# FAN7688.net
KiCad netlist of a schematic drawn in Altium Designer
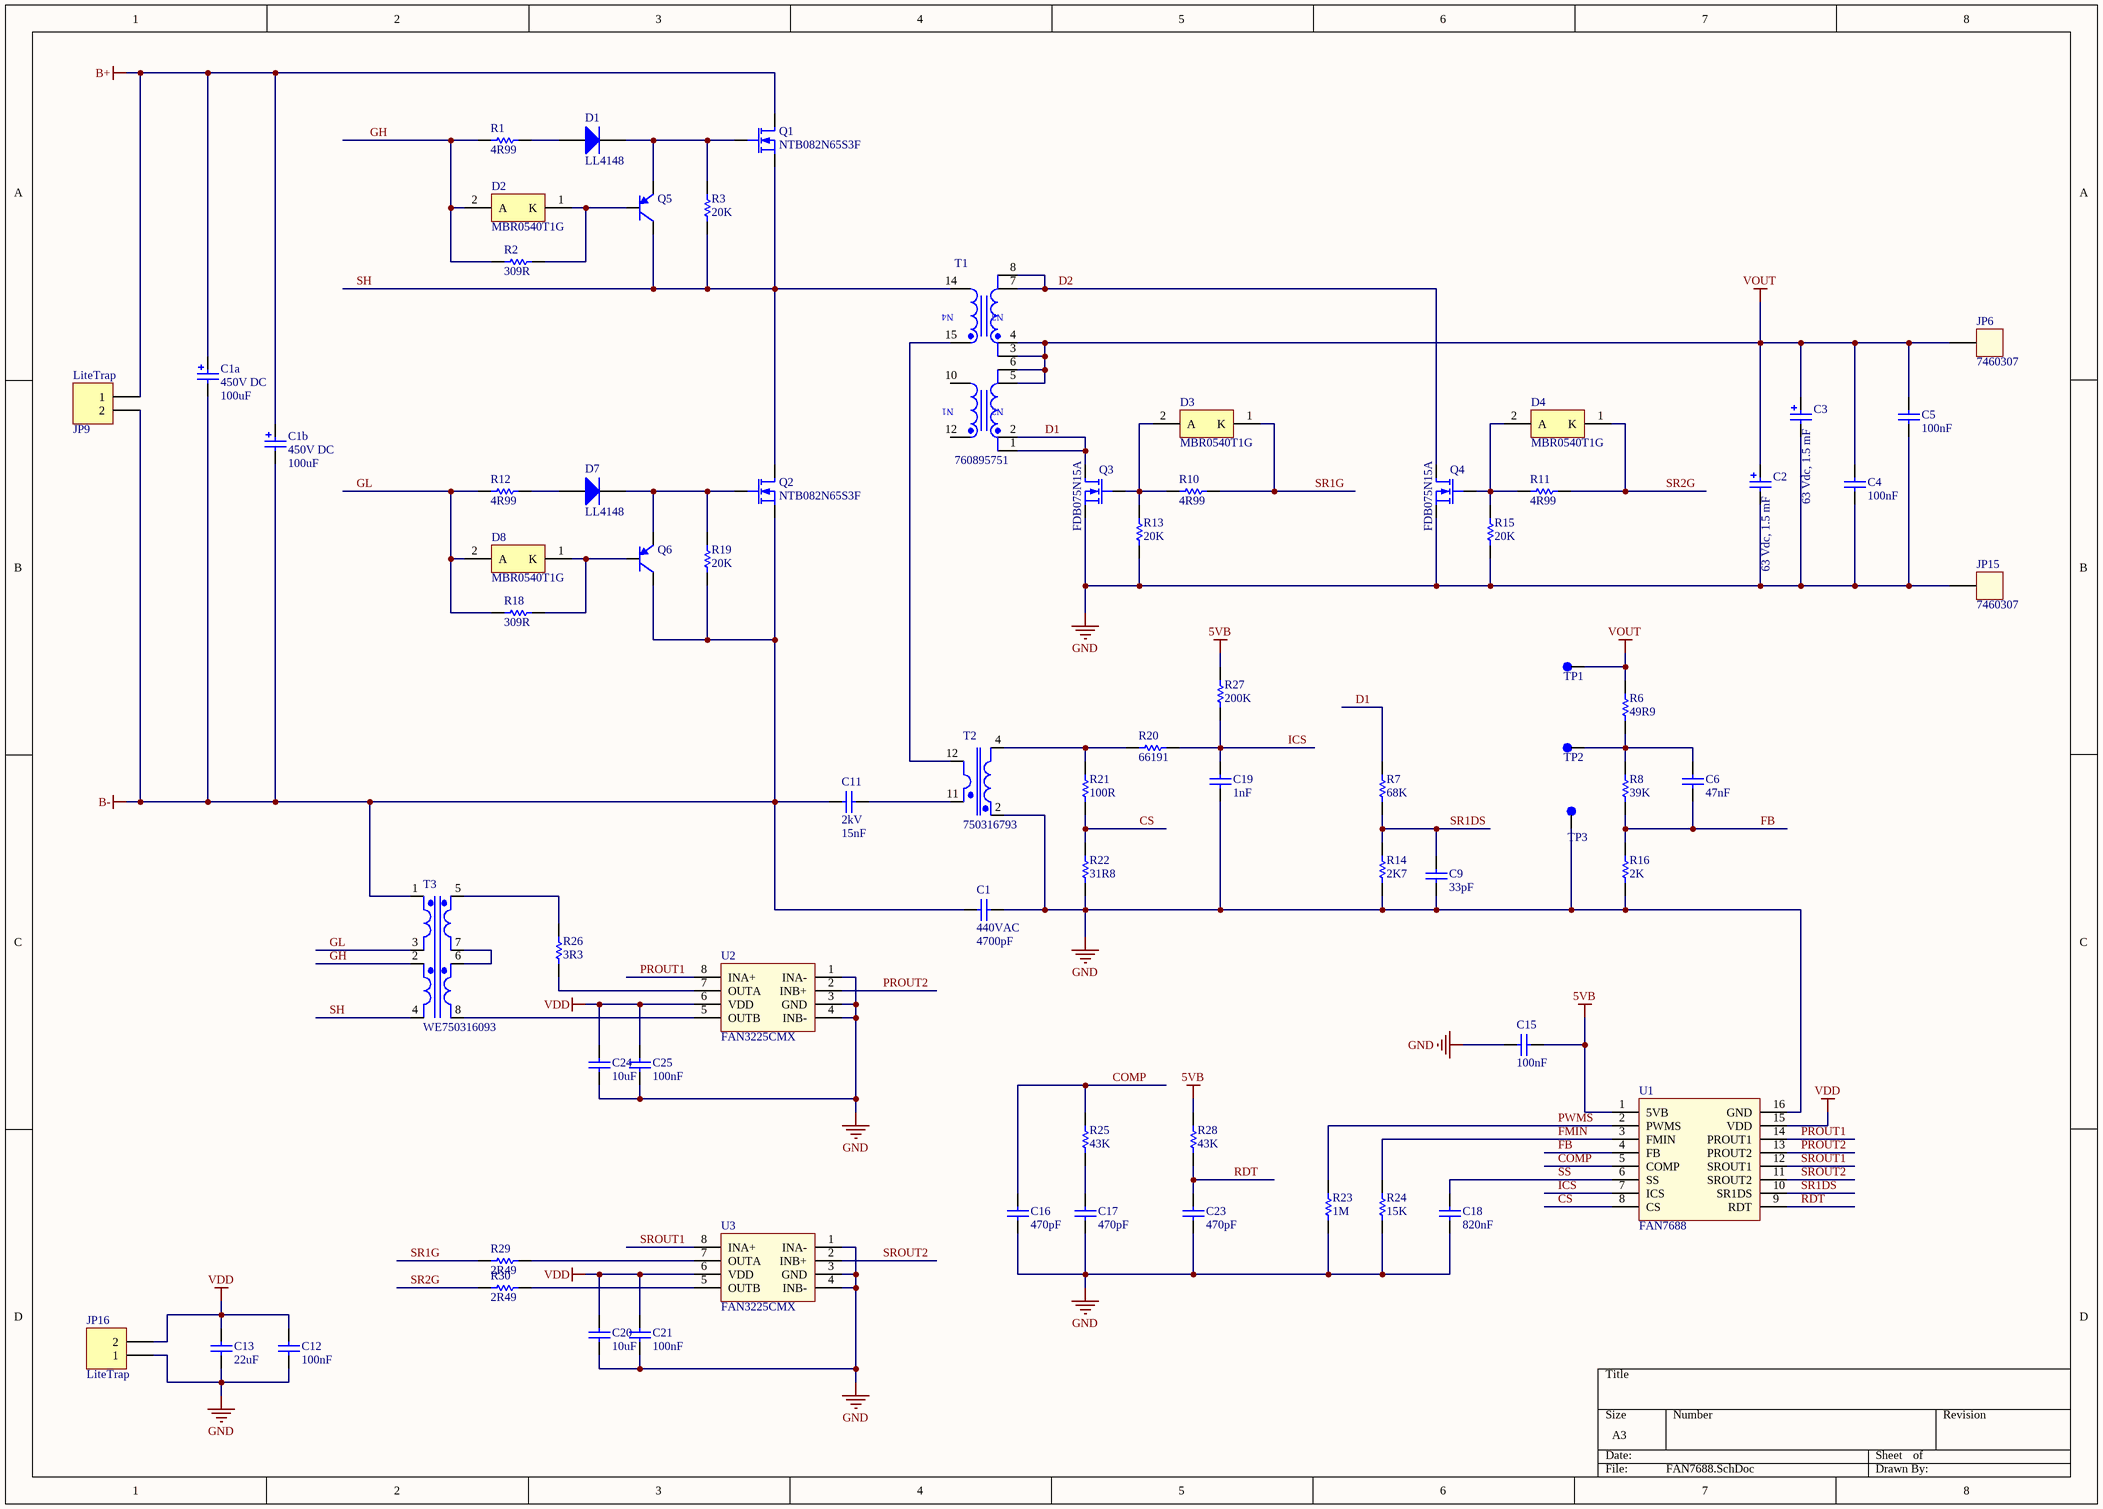
[diagram p0: FAN7688.SchDoc]

(export (version "E")
  (design (tool "Eeschema 10.0.6"))
  (components
    (comp (ref "C1")
      (value "4700pF")
      (footprint "CAP_VY2472M49Y5US63V7")
      (description "4700pF ±20% 440VAC Ceramic Capacitor Y5U (E) Radial, Disc")
      (fields (field (name "MPN") "VY2472M49Y5US63V7") (field (name "VOLTAGE") "440VAC"))
      (libsource (lib "micun") (part "CAP_VY2_4700"))
    )
    (comp (ref "C1a")
      (value "100uF")
      (footprint "WCAP-AT1H_16x35.5x7.5")
      (description "WCAP-AT1H Aluminum Electrolytic Capacitors, size Ф16x35.5mm, 450V DC, 100uF")
      (fields
        (field (name "PART NUMBER") "860241480001")
        (field (name "RATED VOLTAGE") "450V DC")
        (field (name "PUBLISHER") "Wurth Elektronik")
      )
      (libsource (lib "ALTIUM-WCAP-AT1H-rev17a") (part "860241480001"))
    )
    (comp (ref "C1b")
      (value "100uF")
      (footprint "WCAP-AT1H_16x35.5x7.5")
      (description "WCAP-AT1H Aluminum Electrolytic Capacitors, size Ф16x35.5mm, 450V DC, 100uF")
      (fields
        (field (name "PART NUMBER") "860241480001")
        (field (name "RATED VOLTAGE") "450V DC")
        (field (name "PUBLISHER") "Wurth Elektronik")
      )
      (libsource (lib "ALTIUM-WCAP-AT1H-rev17a") (part "860241480001"))
    )
    (comp (ref "C2")
      (value "63 Vdc, 1.5 mF")
      (footprint "WCAP-ATG5_18x31.5x7.5")
      (description "WCAP-ATG5 Aluminum Electrolytic Capacitors, 18x31.5mm, 63 Vdc, 1.5 mF")
      (fields (field (name "PART NUMBER") "860020781027") (field (name "PUBLISHER") "Wurth Elektronik"))
      (libsource (lib "ALTIUM-WCAP-ATG5-rev17a") (part "860020781027"))
    )
    (comp (ref "C3")
      (value "63 Vdc, 1.5 mF")
      (footprint "WCAP-ATG5_18x31.5x7.5")
      (description "WCAP-ATG5 Aluminum Electrolytic Capacitors, 18x31.5mm, 63 Vdc, 1.5 mF")
      (fields (field (name "PART NUMBER") "860020781027") (field (name "PUBLISHER") "Wurth Elektronik"))
      (libsource (lib "ALTIUM-WCAP-ATG5-rev17a") (part "860020781027"))
    )
    (comp (ref "C4")
      (value "100nF")
      (footprint "CAPC1206(3216)75_L")
      (description "Generic capacitor non polarised")
      (fields (field (name "Comment") "CAP"))
      (libsource (lib "micun") (part "CAP"))
    )
    (comp (ref "C5")
      (value "100nF")
      (footprint "CAPC1206(3216)75_L")
      (description "Generic capacitor non polarised")
      (fields (field (name "Comment") "CAP"))
      (libsource (lib "micun") (part "CAP"))
    )
    (comp (ref "C6")
      (value "47nF")
      (footprint "CAPC0805(2012)75_L")
      (description "Generic capacitor non polarised")
      (fields (field (name "Comment") "CAP"))
      (libsource (lib "micun") (part "CAP"))
    )
    (comp (ref "C9")
      (value "33pF")
      (footprint "CAPC0805(2012)75_L")
      (description "Generic capacitor non polarised")
      (fields (field (name "Comment") "CAP"))
      (libsource (lib "micun") (part "CAP"))
    )
    (comp (ref "C11")
      (value "15nF")
      (footprint "CAP_RM15_W9L18")
      (description "0.015µF Film Capacitor 700V 2000V (2kV) Polypropylene (PP), Metallized Radial")
      (fields (field (name "MPN") "B32672L8153J000") (field (name "VOLTAGE") "2kV"))
      (libsource (lib "micun") (part "CAP_MKP_B32672L8153J000"))
    )
    (comp (ref "C12")
      (value "100nF")
      (footprint "CAPC0805(2012)75_L")
      (description "Generic capacitor non polarised")
      (fields (field (name "Comment") "CAP"))
      (libsource (lib "micun") (part "CAP"))
    )
    (comp (ref "C13")
      (value "22uF")
      (footprint "CAPC1206(3216)75_L")
      (description "Generic capacitor non polarised")
      (fields (field (name "Comment") "CAP"))
      (libsource (lib "micun") (part "CAP"))
    )
    (comp (ref "C15")
      (value "100nF")
      (footprint "CAPC0805(2012)75_L")
      (description "Generic capacitor non polarised")
      (fields (field (name "Comment") "CAP"))
      (libsource (lib "micun") (part "CAP"))
    )
    (comp (ref "C16")
      (value "470pF")
      (footprint "CAPC0805(2012)75_L")
      (description "Generic capacitor non polarised")
      (fields (field (name "Comment") "CAP"))
      (libsource (lib "micun") (part "CAP"))
    )
    (comp (ref "C17")
      (value "470pF")
      (footprint "CAPC0805(2012)75_L")
      (description "Generic capacitor non polarised")
      (fields (field (name "Comment") "CAP"))
      (libsource (lib "micun") (part "CAP"))
    )
    (comp (ref "C18")
      (value "820nF")
      (footprint "CAPC0805(2012)75_L")
      (description "Generic capacitor non polarised")
      (fields (field (name "Comment") "CAP"))
      (libsource (lib "micun") (part "CAP"))
    )
    (comp (ref "C19")
      (value "1nF")
      (footprint "CAPC0805(2012)75_L")
      (description "Generic capacitor non polarised")
      (fields (field (name "Comment") "CAP"))
      (libsource (lib "micun") (part "CAP"))
    )
    (comp (ref "C20")
      (value "10uF")
      (footprint "CAPC0805(2012)75_L")
      (description "Generic capacitor non polarised")
      (fields (field (name "Comment") "CAP"))
      (libsource (lib "micun") (part "CAP"))
    )
    (comp (ref "C21")
      (value "100nF")
      (footprint "CAPC0805(2012)75_L")
      (description "Generic capacitor non polarised")
      (fields (field (name "Comment") "CAP"))
      (libsource (lib "micun") (part "CAP"))
    )
    (comp (ref "C23")
      (value "470pF")
      (footprint "CAPC0805(2012)75_L")
      (description "Generic capacitor non polarised")
      (fields (field (name "Comment") "CAP"))
      (libsource (lib "micun") (part "CAP"))
    )
    (comp (ref "C24")
      (value "10uF")
      (footprint "CAPC0805(2012)75_L")
      (description "Generic capacitor non polarised")
      (fields (field (name "Comment") "CAP"))
      (libsource (lib "micun") (part "CAP"))
    )
    (comp (ref "C25")
      (value "100nF")
      (footprint "CAPC0805(2012)75_L")
      (description "Generic capacitor non polarised")
      (fields (field (name "Comment") "CAP"))
      (libsource (lib "micun") (part "CAP"))
    )
    (comp (ref "D1")
      (value "LL4148")
      (footprint "DIOD-SOD-80")
      (description "DIODE GEN PURP 100V 200MA SOD80")
      (libsource (lib "micun") (part "DIOD_GP_LL4148"))
    )
    (comp (ref "D2")
      (value "MBR0540T1G")
      (footprint "ONSC-SOD-123-2-425-04_V")
      (description "Schottky Power Rectifier, 2-Pin SOD-123, Pb-Free, Tape and Reel")
      (fields (field (name "MANUFACTURER") "On Semiconductor"))
      (libsource (lib "Altium Content Vault") (part "ONSC-D-K1A2-2_A"))
    )
    (comp (ref "D3")
      (value "MBR0540T1G")
      (footprint "ONSC-SOD-123-2-425-04_V")
      (description "Schottky Power Rectifier, 2-Pin SOD-123, Pb-Free, Tape and Reel")
      (fields (field (name "MANUFACTURER") "On Semiconductor"))
      (libsource (lib "Altium Content Vault") (part "ONSC-D-K1A2-2_A"))
    )
    (comp (ref "D4")
      (value "MBR0540T1G")
      (footprint "ONSC-SOD-123-2-425-04_V")
      (description "Schottky Power Rectifier, 2-Pin SOD-123, Pb-Free, Tape and Reel")
      (fields (field (name "MANUFACTURER") "On Semiconductor"))
      (libsource (lib "Altium Content Vault") (part "ONSC-D-K1A2-2_A"))
    )
    (comp (ref "D7")
      (value "LL4148")
      (footprint "DIOD-SOD-80")
      (description "DIODE GEN PURP 100V 200MA SOD80")
      (libsource (lib "micun") (part "DIOD_GP_LL4148"))
    )
    (comp (ref "D8")
      (value "MBR0540T1G")
      (footprint "ONSC-SOD-123-2-425-04_V")
      (description "Schottky Power Rectifier, 2-Pin SOD-123, Pb-Free, Tape and Reel")
      (fields (field (name "MANUFACTURER") "On Semiconductor"))
      (libsource (lib "Altium Content Vault") (part "ONSC-D-K1A2-2_A"))
    )
    (comp (ref "JP6")
      (value "7460307")
      (footprint "7460307")
      (description "REDCUBE PRESS-FIT with internal thread, two rows WP-BUTR, M4 - 6 mm")
      (fields (field (name "PUBLISHER") "Wurth Elektronik"))
      (libsource (lib "ALTIUM-WP-BUTR_TWO-ROWS-rev17a") (part "7460307"))
    )
    (comp (ref "JP9")
      (value "LiteTrap")
      (footprint "CONN_MiniLite")
      (description "CONN SSL RCPT 2POS 4MM SOLDER")
      (fields (field (name "MPN") "104188-0210"))
      (libsource (lib "") (part "CONN_LiteTrap_2_1"))
    )
    (comp (ref "JP15")
      (value "7460307")
      (footprint "7460307")
      (description "REDCUBE PRESS-FIT with internal thread, two rows WP-BUTR, M4 - 6 mm")
      (fields (field (name "PUBLISHER") "Wurth Elektronik"))
      (libsource (lib "ALTIUM-WP-BUTR_TWO-ROWS-rev17a") (part "7460307"))
    )
    (comp (ref "JP16")
      (value "LiteTrap")
      (footprint "CONN_MiniLite")
      (description "CONN SSL RCPT 2POS 4MM SOLDER")
      (fields (field (name "MPN") "104188-0210"))
      (libsource (lib "micun") (part "CONN_LiteTrap_2"))
    )
    (comp (ref "Q1")
      (value "NTB082N65S3F")
      (footprint "D2PAK_L")
      (description "N-Channel 650V 40A (Tc) 313W (Tc) Surface Mount D2PAK (TO-263)")
      (libsource (lib "micun") (part "TRAN_NTB082N65S3F"))
    )
    (comp (ref "Q2")
      (value "NTB082N65S3F")
      (footprint "D2PAK_L")
      (description "N-Channel 650V 40A (Tc) 313W (Tc) Surface Mount D2PAK (TO-263)")
      (libsource (lib "micun") (part "TRAN_NTB082N65S3F"))
    )
    (comp (ref "Q3")
      (value "FDB075N15A")
      (footprint "D2PAK_L")
      (description "N-Channel 150V 110A (Tc) 333W (Tc) Surface Mount D2PAK (TO-263)")
      (libsource (lib "micun") (part "TRAN_FDB075N15A"))
    )
    (comp (ref "Q4")
      (value "FDB075N15A")
      (footprint "D2PAK_L")
      (description "N-Channel 150V 110A (Tc) 333W (Tc) Surface Mount D2PAK (TO-263)")
      (libsource (lib "micun") (part "TRAN_FDB075N15A"))
    )
    (comp (ref "Q5")
      (value "ZXTP19060CFFTA")
      (footprint "DIOD-SOT23F-3_V")
      (description "Bipolar (BJT) Transistor PNP 60V 4A 180MHz 1.5W Surface Mount SOT-23F")
      (libsource (lib "micun") (part "TRAN_ZXTP19060CFFTA"))
    )
    (comp (ref "Q6")
      (value "ZXTP19060CFFTA")
      (footprint "DIOD-SOT23F-3_V")
      (description "Bipolar (BJT) Transistor PNP 60V 4A 180MHz 1.5W Surface Mount SOT-23F")
      (libsource (lib "micun") (part "TRAN_ZXTP19060CFFTA"))
    )
    (comp (ref "R1")
      (value "4R99")
      (footprint "RESC0805(2012)_L")
      (description "Generic resistor")
      (fields (field (name "Comment") "RES"))
      (libsource (lib "micun") (part "RES"))
    )
    (comp (ref "R2")
      (value "309R")
      (footprint "RESC0805(2012)_L")
      (description "Generic resistor")
      (fields (field (name "Comment") "RES"))
      (libsource (lib "micun") (part "RES"))
    )
    (comp (ref "R3")
      (value "20K")
      (footprint "RESC0805(2012)_L")
      (description "Generic resistor")
      (fields (field (name "Comment") "RES"))
      (libsource (lib "micun") (part "RES"))
    )
    (comp (ref "R6")
      (value "49R9")
      (footprint "RESC0805(2012)_L")
      (description "Generic resistor")
      (fields (field (name "Comment") "RES"))
      (libsource (lib "micun") (part "RES"))
    )
    (comp (ref "R7")
      (value "68K")
      (footprint "RESC0805(2012)_L")
      (description "Generic resistor")
      (fields (field (name "Comment") "RES"))
      (libsource (lib "micun") (part "RES"))
    )
    (comp (ref "R8")
      (value "39K")
      (footprint "RESC0805(2012)_L")
      (description "Generic resistor")
      (fields (field (name "Comment") "RES"))
      (libsource (lib "micun") (part "RES"))
    )
    (comp (ref "R10")
      (value "4R99")
      (footprint "RESC0805(2012)_L")
      (description "Generic resistor")
      (fields (field (name "Comment") "RES"))
      (libsource (lib "micun") (part "RES"))
    )
    (comp (ref "R11")
      (value "4R99")
      (footprint "RESC0805(2012)_L")
      (description "Generic resistor")
      (fields (field (name "Comment") "RES"))
      (libsource (lib "micun") (part "RES"))
    )
    (comp (ref "R12")
      (value "4R99")
      (footprint "RESC0805(2012)_L")
      (description "Generic resistor")
      (fields (field (name "Comment") "RES"))
      (libsource (lib "micun") (part "RES"))
    )
    (comp (ref "R13")
      (value "20K")
      (footprint "RESC0805(2012)_L")
      (description "Generic resistor")
      (fields (field (name "Comment") "RES"))
      (libsource (lib "micun") (part "RES"))
    )
    (comp (ref "R14")
      (value "2K7")
      (footprint "RESC0805(2012)_L")
      (description "Generic resistor")
      (fields (field (name "Comment") "RES"))
      (libsource (lib "micun") (part "RES"))
    )
    (comp (ref "R15")
      (value "20K")
      (footprint "RESC0805(2012)_L")
      (description "Generic resistor")
      (fields (field (name "Comment") "RES"))
      (libsource (lib "micun") (part "RES"))
    )
    (comp (ref "R16")
      (value "2K")
      (footprint "RESC0805(2012)_L")
      (description "Generic resistor")
      (fields (field (name "Comment") "RES"))
      (libsource (lib "micun") (part "RES"))
    )
    (comp (ref "R18")
      (value "309R")
      (footprint "RESC0805(2012)_L")
      (description "Generic resistor")
      (fields (field (name "Comment") "RES"))
      (libsource (lib "micun") (part "RES"))
    )
    (comp (ref "R19")
      (value "20K")
      (footprint "RESC0805(2012)_L")
      (description "Generic resistor")
      (fields (field (name "Comment") "RES"))
      (libsource (lib "micun") (part "RES"))
    )
    (comp (ref "R20")
      (value "66191")
      (footprint "RESC0805(2012)_L")
      (description "Generic resistor")
      (fields (field (name "Comment") "RES"))
      (libsource (lib "micun") (part "RES"))
    )
    (comp (ref "R21")
      (value "100R")
      (footprint "RESC0805(2012)_L")
      (description "Generic resistor")
      (fields (field (name "Comment") "RES"))
      (libsource (lib "micun") (part "RES"))
    )
    (comp (ref "R22")
      (value "31R8")
      (footprint "RESC0805(2012)_L")
      (description "Generic resistor")
      (fields (field (name "Comment") "RES"))
      (libsource (lib "micun") (part "RES"))
    )
    (comp (ref "R23")
      (value "1M")
      (footprint "RESC0805(2012)_L")
      (description "Generic resistor")
      (fields (field (name "Comment") "RES"))
      (libsource (lib "micun") (part "RES"))
    )
    (comp (ref "R24")
      (value "15K")
      (footprint "RESC0805(2012)_L")
      (description "Generic resistor")
      (fields (field (name "Comment") "RES"))
      (libsource (lib "micun") (part "RES"))
    )
    (comp (ref "R25")
      (value "43K")
      (footprint "RESC0805(2012)_L")
      (description "Generic resistor")
      (fields (field (name "Comment") "RES"))
      (libsource (lib "micun") (part "RES"))
    )
    (comp (ref "R26")
      (value "3R3")
      (footprint "RESC0805(2012)_L")
      (description "Generic resistor")
      (fields (field (name "Comment") "RES"))
      (libsource (lib "micun") (part "RES"))
    )
    (comp (ref "R27")
      (value "200K")
      (footprint "RESC0805(2012)_L")
      (description "Generic resistor")
      (fields (field (name "Comment") "RES"))
      (libsource (lib "micun") (part "RES"))
    )
    (comp (ref "R28")
      (value "43K")
      (footprint "RESC0805(2012)_L")
      (description "Generic resistor")
      (fields (field (name "Comment") "RES"))
      (libsource (lib "micun") (part "RES"))
    )
    (comp (ref "R29")
      (value "2R49")
      (footprint "RESC0805(2012)_L")
      (description "Generic resistor")
      (fields (field (name "Comment") "RES"))
      (libsource (lib "micun") (part "RES"))
    )
    (comp (ref "R30")
      (value "2R49")
      (footprint "RESC0805(2012)_L")
      (description "Generic resistor")
      (fields (field (name "Comment") "RES"))
      (libsource (lib "micun") (part "RES"))
    )
    (comp (ref "T1")
      (value "760895751")
      (footprint "WE-LLCR_ETD44")
      (description "WE-LLCR Resonant Converter, size ETD44, 600uH, 27:6:6:2 , 250W")
      (fields (field (name "PUBLISHER") "Wurth Elektronik"))
      (libsource (lib "ALTIUM-WE-LLCR-rev17a") (part "760895751"))
    )
    (comp (ref "T2")
      (value "750316793")
      (footprint "WE_750316793")
      (description "MID-SNS Current Sense Transformers")
      (libsource (lib "micun") (part "TRANS_WE750316793"))
    )
    (comp (ref "T3")
      (value "WE750316093")
      (footprint "WE_750316093")
      (description "MID-GDT Gate Drive Transformers")
      (fields (field (name "MPN") "750316093"))
      (libsource (lib "micun") (part "TRANS_WE750316093"))
    )
    (comp (ref "TP1")
      (value "MECH_Testpoint")
      (footprint "MECH_TP_39_mil")
      (description "Testpoint")
      (libsource (lib "micun") (part "MECH_Testpoint"))
    )
    (comp (ref "TP2")
      (value "MECH_Testpoint")
      (footprint "MECH_TP_39_mil")
      (description "Testpoint")
      (libsource (lib "micun") (part "MECH_Testpoint"))
    )
    (comp (ref "TP3")
      (value "MECH_Testpoint")
      (footprint "MECH_TP_39_mil")
      (description "Testpoint")
      (libsource (lib "micun") (part "MECH_Testpoint"))
    )
    (comp (ref "U1")
      (value "FAN7688")
      (footprint "ONSC-SOEIAJ-16-966-01_L")
      (description "Power Supply Controller Secondary-Side Controller, Synchronous Rectifier 16-SOP")
      (fields (field (name "MPN") "FAN7688SJX"))
      (libsource (lib "micun") (part "IC-PMIC-FAN7688"))
    )
    (comp (ref "U2")
      (value "FAN3225CMX")
      (footprint "SOIC8_L")
      (description "Low-Side Gate Driver IC Inverting, Non-Inverting 8-SOIC")
      (libsource (lib "micun") (part "IC-PMIC-FAN3225CMX"))
    )
    (comp (ref "U3")
      (value "FAN3225CMX")
      (footprint "SOIC8_L")
      (description "Low-Side Gate Driver IC Inverting, Non-Inverting 8-SOIC")
      (libsource (lib "micun") (part "IC-PMIC-FAN3225CMX"))
    )
  )
  (nets
    (net (code "1") (name "/COMP") (class "Default")
      (node (ref "C16") (pin "2") (pinfunction "2_2") (pintype "passive"))
      (node (ref "R25") (pin "2") (pinfunction "2_2") (pintype "passive"))
      (node (ref "U1") (pin "5") (pinfunction "COMP_5") (pintype "passive"))
    )
    (net (code "2") (name "/CS") (class "Default")
      (node (ref "R21") (pin "1") (pinfunction "1_1") (pintype "passive"))
      (node (ref "R22") (pin "2") (pinfunction "2_2") (pintype "passive"))
      (node (ref "U1") (pin "8") (pinfunction "CS_8") (pintype "passive"))
    )
    (net (code "3") (name "/D1") (class "Default")
      (node (ref "Q3") (pin "4") (pinfunction "D_4") (pintype "passive"))
      (node (ref "R7") (pin "2") (pinfunction "2_2") (pintype "passive"))
      (node (ref "T1") (pin "1") (pinfunction "1_1") (pintype "passive"))
      (node (ref "T1") (pin "2") (pinfunction "2_2") (pintype "passive"))
    )
    (net (code "4") (name "/D2") (class "Default")
      (node (ref "Q4") (pin "4") (pinfunction "D_4") (pintype "passive"))
      (node (ref "T1") (pin "7") (pinfunction "7_7") (pintype "passive"))
      (node (ref "T1") (pin "8") (pinfunction "8_8") (pintype "passive"))
    )
    (net (code "5") (name "/FB") (class "Default")
      (node (ref "C6") (pin "1") (pinfunction "1_1") (pintype "passive"))
      (node (ref "R16") (pin "2") (pinfunction "2_2") (pintype "passive"))
      (node (ref "R8") (pin "1") (pinfunction "1_1") (pintype "passive"))
      (node (ref "U1") (pin "4") (pinfunction "FB_4") (pintype "passive"))
    )
    (net (code "6") (name "/FMIN") (class "Default")
      (node (ref "R24") (pin "2") (pinfunction "2_2") (pintype "passive"))
      (node (ref "U1") (pin "3") (pinfunction "FMIN_3") (pintype "passive"))
    )
    (net (code "7") (name "/GH") (class "Default")
      (node (ref "D2") (pin "2") (pinfunction "A_2") (pintype "passive"))
      (node (ref "R1") (pin "1") (pinfunction "1_1") (pintype "passive"))
      (node (ref "R2") (pin "2") (pinfunction "2_2") (pintype "passive"))
      (node (ref "T3") (pin "2") (pinfunction "2_2") (pintype "passive"))
    )
    (net (code "8") (name "/GL") (class "Default")
      (node (ref "D8") (pin "2") (pinfunction "A_2") (pintype "passive"))
      (node (ref "R12") (pin "1") (pinfunction "1_1") (pintype "passive"))
      (node (ref "R18") (pin "2") (pinfunction "2_2") (pintype "passive"))
      (node (ref "T3") (pin "3") (pinfunction "3_3") (pintype "passive"))
    )
    (net (code "9") (name "/ICS") (class "Default")
      (node (ref "C19") (pin "2") (pinfunction "2_2") (pintype "passive"))
      (node (ref "R20") (pin "2") (pinfunction "2_2") (pintype "passive"))
      (node (ref "R27") (pin "1") (pinfunction "1_1") (pintype "passive"))
      (node (ref "U1") (pin "7") (pinfunction "ICS_7") (pintype "passive"))
    )
    (net (code "10") (name "/PROUT1") (class "Default")
      (node (ref "U1") (pin "14") (pinfunction "PROUT1_14") (pintype "passive"))
      (node (ref "U2") (pin "8") (pinfunction "INA+_8") (pintype "passive"))
    )
    (net (code "11") (name "/PROUT2") (class "Default")
      (node (ref "U1") (pin "13") (pinfunction "PROUT2_13") (pintype "passive"))
      (node (ref "U2") (pin "2") (pinfunction "INB+_2") (pintype "passive"))
    )
    (net (code "12") (name "/PWMS") (class "Default")
      (node (ref "R23") (pin "2") (pinfunction "2_2") (pintype "passive"))
      (node (ref "U1") (pin "2") (pinfunction "PWMS_2") (pintype "passive"))
    )
    (net (code "13") (name "/RDT") (class "Default")
      (node (ref "C23") (pin "2") (pinfunction "2_2") (pintype "passive"))
      (node (ref "R28") (pin "1") (pinfunction "1_1") (pintype "passive"))
      (node (ref "U1") (pin "9") (pinfunction "RDT_9") (pintype "passive"))
    )
    (net (code "14") (name "/SH") (class "Default")
      (node (ref "Q1") (pin "3") (pinfunction "S_3") (pintype "passive"))
      (node (ref "Q2") (pin "4") (pinfunction "D_4") (pintype "passive"))
      (node (ref "Q5") (pin "3") (pinfunction "C_3") (pintype "passive"))
      (node (ref "R3") (pin "1") (pinfunction "1_1") (pintype "passive"))
      (node (ref "T1") (pin "14") (pinfunction "14_14") (pintype "passive"))
      (node (ref "T3") (pin "4") (pinfunction "4_4") (pintype "passive"))
    )
    (net (code "15") (name "/SR1DS") (class "Default")
      (node (ref "C9") (pin "2") (pinfunction "2_2") (pintype "passive"))
      (node (ref "R14") (pin "2") (pinfunction "2_2") (pintype "passive"))
      (node (ref "R7") (pin "1") (pinfunction "1_1") (pintype "passive"))
      (node (ref "U1") (pin "10") (pinfunction "SR1DS_10") (pintype "passive"))
    )
    (net (code "16") (name "/SR1G") (class "Default")
      (node (ref "D3") (pin "1") (pinfunction "K_1") (pintype "passive"))
      (node (ref "R10") (pin "2") (pinfunction "2_2") (pintype "passive"))
      (node (ref "R29") (pin "1") (pinfunction "1_1") (pintype "passive"))
    )
    (net (code "17") (name "/SR2G") (class "Default")
      (node (ref "D4") (pin "1") (pinfunction "K_1") (pintype "passive"))
      (node (ref "R11") (pin "2") (pinfunction "2_2") (pintype "passive"))
      (node (ref "R30") (pin "1") (pinfunction "1_1") (pintype "passive"))
    )
    (net (code "18") (name "/SROUT1") (class "Default")
      (node (ref "U1") (pin "12") (pinfunction "SROUT1_12") (pintype "passive"))
      (node (ref "U3") (pin "8") (pinfunction "INA+_8") (pintype "passive"))
    )
    (net (code "19") (name "/SROUT2") (class "Default")
      (node (ref "U1") (pin "11") (pinfunction "SROUT2_11") (pintype "passive"))
      (node (ref "U3") (pin "2") (pinfunction "INB+_2") (pintype "passive"))
    )
    (net (code "20") (name "/SS") (class "Default")
      (node (ref "C18") (pin "2") (pinfunction "2_2") (pintype "passive"))
      (node (ref "U1") (pin "6") (pinfunction "SS_6") (pintype "passive"))
    )
    (net (code "21") (name "5VB") (class "Default")
      (node (ref "C15") (pin "1") (pinfunction "1_1") (pintype "passive"))
      (node (ref "R27") (pin "2") (pinfunction "2_2") (pintype "passive"))
      (node (ref "R28") (pin "2") (pinfunction "2_2") (pintype "passive"))
      (node (ref "U1") (pin "1") (pinfunction "5VB_1") (pintype "power_in"))
    )
    (net (code "22") (name "B+") (class "Default")
      (node (ref "C1a") (pin "1") (pinfunction "P_1") (pintype "passive"))
      (node (ref "C1b") (pin "1") (pinfunction "P_1") (pintype "passive"))
      (node (ref "JP9") (pin "1") (pinfunction "1_1") (pintype "passive"))
      (node (ref "Q1") (pin "4") (pinfunction "D_4") (pintype "passive"))
    )
    (net (code "23") (name "B-") (class "Default")
      (node (ref "C1") (pin "1") (pinfunction "1_1") (pintype "passive"))
      (node (ref "C11") (pin "1") (pinfunction "1_1") (pintype "passive"))
      (node (ref "C1a") (pin "2") (pinfunction "N_2") (pintype "passive"))
      (node (ref "C1b") (pin "2") (pinfunction "N_2") (pintype "passive"))
      (node (ref "JP9") (pin "2") (pinfunction "2_2") (pintype "passive"))
      (node (ref "Q2") (pin "3") (pinfunction "S_3") (pintype "passive"))
      (node (ref "Q6") (pin "3") (pinfunction "C_3") (pintype "passive"))
      (node (ref "R19") (pin "1") (pinfunction "1_1") (pintype "passive"))
      (node (ref "T3") (pin "1") (pinfunction "1_1") (pintype "passive"))
    )
    (net (code "24") (name "GND") (class "Default")
      (node (ref "C1") (pin "2") (pinfunction "2_2") (pintype "passive"))
      (node (ref "C12") (pin "1") (pinfunction "1_1") (pintype "passive"))
      (node (ref "C13") (pin "1") (pinfunction "1_1") (pintype "passive"))
      (node (ref "C15") (pin "2") (pinfunction "2_2") (pintype "passive"))
      (node (ref "C16") (pin "1") (pinfunction "1_1") (pintype "passive"))
      (node (ref "C17") (pin "1") (pinfunction "1_1") (pintype "passive"))
      (node (ref "C18") (pin "1") (pinfunction "1_1") (pintype "passive"))
      (node (ref "C19") (pin "1") (pinfunction "1_1") (pintype "passive"))
      (node (ref "C2") (pin "2") (pinfunction "N_2") (pintype "passive"))
      (node (ref "C20") (pin "1") (pinfunction "1_1") (pintype "passive"))
      (node (ref "C21") (pin "1") (pinfunction "1_1") (pintype "passive"))
      (node (ref "C23") (pin "1") (pinfunction "1_1") (pintype "passive"))
      (node (ref "C24") (pin "1") (pinfunction "1_1") (pintype "passive"))
      (node (ref "C25") (pin "1") (pinfunction "1_1") (pintype "passive"))
      (node (ref "C3") (pin "2") (pinfunction "N_2") (pintype "passive"))
      (node (ref "C4") (pin "1") (pinfunction "1_1") (pintype "passive"))
      (node (ref "C5") (pin "1") (pinfunction "1_1") (pintype "passive"))
      (node (ref "C9") (pin "1") (pinfunction "1_1") (pintype "passive"))
      (node (ref "JP15") (pin "1") (pinfunction "1_1") (pintype "passive"))
      (node (ref "JP16") (pin "1") (pinfunction "1_1") (pintype "passive"))
      (node (ref "Q3") (pin "3") (pinfunction "S_3") (pintype "passive"))
      (node (ref "Q4") (pin "3") (pinfunction "S_3") (pintype "passive"))
      (node (ref "R13") (pin "1") (pinfunction "1_1") (pintype "passive"))
      (node (ref "R14") (pin "1") (pinfunction "1_1") (pintype "passive"))
      (node (ref "R15") (pin "1") (pinfunction "1_1") (pintype "passive"))
      (node (ref "R16") (pin "1") (pinfunction "1_1") (pintype "passive"))
      (node (ref "R22") (pin "1") (pinfunction "1_1") (pintype "passive"))
      (node (ref "R23") (pin "1") (pinfunction "1_1") (pintype "passive"))
      (node (ref "R24") (pin "1") (pinfunction "1_1") (pintype "passive"))
      (node (ref "T2") (pin "2") (pinfunction "2_2") (pintype "passive"))
      (node (ref "TP3") (pin "1") (pinfunction "Pin1_1") (pintype "passive"))
      (node (ref "U1") (pin "16") (pinfunction "GND_16") (pintype "power_in"))
      (node (ref "U2") (pin "1") (pinfunction "INA-_1") (pintype "passive"))
      (node (ref "U2") (pin "3") (pinfunction "GND_3") (pintype "power_in"))
      (node (ref "U2") (pin "4") (pinfunction "INB-_4") (pintype "passive"))
      (node (ref "U3") (pin "1") (pinfunction "INA-_1") (pintype "passive"))
      (node (ref "U3") (pin "3") (pinfunction "GND_3") (pintype "power_in"))
      (node (ref "U3") (pin "4") (pinfunction "INB-_4") (pintype "passive"))
    )
    (net (code "25") (name "Net-(C11-Pad2)") (class "Default")
      (node (ref "C11") (pin "2") (pinfunction "2_2") (pintype "passive"))
      (node (ref "T2") (pin "11") (pinfunction "11_11") (pintype "passive"))
    )
    (net (code "26") (name "Net-(C17-Pad2)") (class "Default")
      (node (ref "C17") (pin "2") (pinfunction "2_2") (pintype "passive"))
      (node (ref "R25") (pin "1") (pinfunction "1_1") (pintype "passive"))
    )
    (net (code "27") (name "Net-(D1-A)") (class "Default")
      (node (ref "D1") (pin "1") (pinfunction "A_1") (pintype "passive"))
      (node (ref "R1") (pin "2") (pinfunction "2_2") (pintype "passive"))
    )
    (net (code "28") (name "Net-(D1-K)") (class "Default")
      (node (ref "D1") (pin "2") (pinfunction "K_2") (pintype "passive"))
      (node (ref "Q1") (pin "1") (pinfunction "G_1") (pintype "passive"))
      (node (ref "Q5") (pin "2") (pinfunction "E_2") (pintype "passive"))
      (node (ref "R3") (pin "2") (pinfunction "2_2") (pintype "passive"))
    )
    (net (code "29") (name "Net-(D2-K)") (class "Default")
      (node (ref "D2") (pin "1") (pinfunction "K_1") (pintype "passive"))
      (node (ref "Q5") (pin "1") (pinfunction "B_1") (pintype "passive"))
      (node (ref "R2") (pin "1") (pinfunction "1_1") (pintype "passive"))
    )
    (net (code "30") (name "Net-(D3-A)") (class "Default")
      (node (ref "D3") (pin "2") (pinfunction "A_2") (pintype "passive"))
      (node (ref "Q3") (pin "1") (pinfunction "G_1") (pintype "passive"))
      (node (ref "R10") (pin "1") (pinfunction "1_1") (pintype "passive"))
      (node (ref "R13") (pin "2") (pinfunction "2_2") (pintype "passive"))
    )
    (net (code "31") (name "Net-(D4-A)") (class "Default")
      (node (ref "D4") (pin "2") (pinfunction "A_2") (pintype "passive"))
      (node (ref "Q4") (pin "1") (pinfunction "G_1") (pintype "passive"))
      (node (ref "R11") (pin "1") (pinfunction "1_1") (pintype "passive"))
      (node (ref "R15") (pin "2") (pinfunction "2_2") (pintype "passive"))
    )
    (net (code "32") (name "Net-(D7-A)") (class "Default")
      (node (ref "D7") (pin "1") (pinfunction "A_1") (pintype "passive"))
      (node (ref "R12") (pin "2") (pinfunction "2_2") (pintype "passive"))
    )
    (net (code "33") (name "Net-(D7-K)") (class "Default")
      (node (ref "D7") (pin "2") (pinfunction "K_2") (pintype "passive"))
      (node (ref "Q2") (pin "1") (pinfunction "G_1") (pintype "passive"))
      (node (ref "Q6") (pin "2") (pinfunction "E_2") (pintype "passive"))
      (node (ref "R19") (pin "2") (pinfunction "2_2") (pintype "passive"))
    )
    (net (code "34") (name "Net-(D8-K)") (class "Default")
      (node (ref "D8") (pin "1") (pinfunction "K_1") (pintype "passive"))
      (node (ref "Q6") (pin "1") (pinfunction "B_1") (pintype "passive"))
      (node (ref "R18") (pin "1") (pinfunction "1_1") (pintype "passive"))
    )
    (net (code "35") (name "Net-(R20-Pad1)") (class "Default")
      (node (ref "R20") (pin "1") (pinfunction "1_1") (pintype "passive"))
      (node (ref "R21") (pin "2") (pinfunction "2_2") (pintype "passive"))
      (node (ref "T2") (pin "4") (pinfunction "4_4") (pintype "passive"))
    )
    (net (code "36") (name "Net-(R26-Pad2)") (class "Default")
      (node (ref "R26") (pin "2") (pinfunction "2_2") (pintype "passive"))
      (node (ref "T3") (pin "5") (pinfunction "5_5") (pintype "passive"))
    )
    (net (code "37") (name "Net-(T1-Pad15)") (class "Default")
      (node (ref "T1") (pin "15") (pinfunction "15_15") (pintype "passive"))
      (node (ref "T2") (pin "12") (pinfunction "12_12") (pintype "passive"))
    )
    (net (code "38") (name "Net-(T3-Pad6)") (class "Default")
      (node (ref "T3") (pin "6") (pinfunction "6_6") (pintype "passive"))
      (node (ref "T3") (pin "7") (pinfunction "7_7") (pintype "passive"))
    )
    (net (code "39") (name "Net-(TP2-Pin1)") (class "Default")
      (node (ref "C6") (pin "2") (pinfunction "2_2") (pintype "passive"))
      (node (ref "R6") (pin "1") (pinfunction "1_1") (pintype "passive"))
      (node (ref "R8") (pin "2") (pinfunction "2_2") (pintype "passive"))
      (node (ref "TP2") (pin "1") (pinfunction "Pin1_1") (pintype "passive"))
    )
    (net (code "40") (name "Net-(U2-OUTA)") (class "Default")
      (node (ref "R26") (pin "1") (pinfunction "1_1") (pintype "passive"))
      (node (ref "U2") (pin "7") (pinfunction "OUTA_7") (pintype "passive"))
    )
    (net (code "41") (name "Net-(U2-OUTB)") (class "Default")
      (node (ref "T3") (pin "8") (pinfunction "8_8") (pintype "passive"))
      (node (ref "U2") (pin "5") (pinfunction "OUTB_5") (pintype "passive"))
    )
    (net (code "42") (name "Net-(U3-OUTA)") (class "Default")
      (node (ref "R29") (pin "2") (pinfunction "2_2") (pintype "passive"))
      (node (ref "U3") (pin "7") (pinfunction "OUTA_7") (pintype "passive"))
    )
    (net (code "43") (name "Net-(U3-OUTB)") (class "Default")
      (node (ref "R30") (pin "2") (pinfunction "2_2") (pintype "passive"))
      (node (ref "U3") (pin "5") (pinfunction "OUTB_5") (pintype "passive"))
    )
    (net (code "44") (name "VDD") (class "Default")
      (node (ref "C12") (pin "2") (pinfunction "2_2") (pintype "passive"))
      (node (ref "C13") (pin "2") (pinfunction "2_2") (pintype "passive"))
      (node (ref "C20") (pin "2") (pinfunction "2_2") (pintype "passive"))
      (node (ref "C21") (pin "2") (pinfunction "2_2") (pintype "passive"))
      (node (ref "C24") (pin "2") (pinfunction "2_2") (pintype "passive"))
      (node (ref "C25") (pin "2") (pinfunction "2_2") (pintype "passive"))
      (node (ref "JP16") (pin "2") (pinfunction "2_2") (pintype "passive"))
      (node (ref "U1") (pin "15") (pinfunction "VDD_15") (pintype "power_in"))
      (node (ref "U2") (pin "6") (pinfunction "VDD_6") (pintype "power_in"))
      (node (ref "U3") (pin "6") (pinfunction "VDD_6") (pintype "power_in"))
    )
    (net (code "45") (name "VOUT") (class "Default")
      (node (ref "C2") (pin "1") (pinfunction "P_1") (pintype "passive"))
      (node (ref "C3") (pin "1") (pinfunction "P_1") (pintype "passive"))
      (node (ref "C4") (pin "2") (pinfunction "2_2") (pintype "passive"))
      (node (ref "C5") (pin "2") (pinfunction "2_2") (pintype "passive"))
      (node (ref "JP6") (pin "1") (pinfunction "1_1") (pintype "passive"))
      (node (ref "R6") (pin "2") (pinfunction "2_2") (pintype "passive"))
      (node (ref "T1") (pin "3") (pinfunction "3_3") (pintype "passive"))
      (node (ref "T1") (pin "4") (pinfunction "4_4") (pintype "passive"))
      (node (ref "T1") (pin "5") (pinfunction "5_5") (pintype "passive"))
      (node (ref "T1") (pin "6") (pinfunction "6_6") (pintype "passive"))
      (node (ref "TP1") (pin "1") (pinfunction "Pin1_1") (pintype "passive"))
    )
    (net (code "46") (name "unconnected-(T1-Pad10)") (class "Default")
      (node (ref "T1") (pin "10") (pinfunction "10_10") (pintype "passive"))
    )
    (net (code "47") (name "unconnected-(T1-Pad12)") (class "Default")
      (node (ref "T1") (pin "12") (pinfunction "12_12") (pintype "passive"))
    )
  )
)
